# Sheet1.net
KiCad netlist of a schematic drawn in Altium Designer
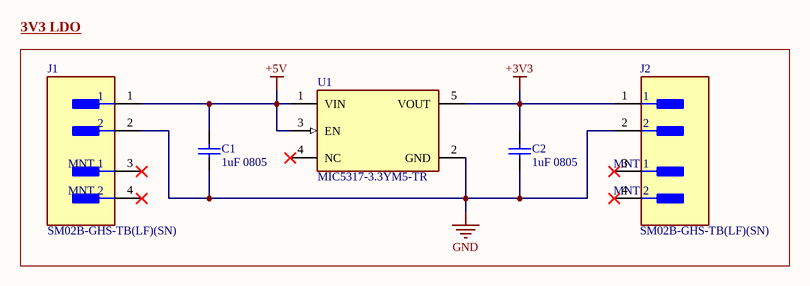
[diagram p0: Sheet1.SchDoc]

(export (version "E")
  (design (tool "Eeschema 10.0.6"))
  (components
    (comp (ref "C1")
      (value "1uF 0805")
      (footprint "CAPC2013X140X50NL20T25")
      (fields
        (field (name "PART NUMBER") "0805YD105MAT2A")
        (field (name "MANUFACTURER") "AVX Interconnect / Elco")
      )
      (libsource (lib "Altium Content Vault") (part "CAP"))
    )
    (comp (ref "C2")
      (value "1uF 0805")
      (footprint "CAPC2013X140X50NL20T25")
      (fields
        (field (name "PART NUMBER") "0805YD105MAT2A")
        (field (name "MANUFACTURER") "AVX Interconnect / Elco")
      )
      (libsource (lib "Altium Content Vault") (part "CAP"))
    )
    (comp (ref "J1")
      (value "SM02B-GHS-TB(LF)(SN)")
      (footprint "FP-SM02B-GHS-TB_LF_SN-MFG")
      (description "CONN HEADER SMD R/A 2POS 1.25MM")
      (libsource (lib "") (part "56ec3178a87b3978bdc1b3682cd516a_1"))
    )
    (comp (ref "J2")
      (value "SM02B-GHS-TB(LF)(SN)")
      (footprint "FP-SM02B-GHS-TB_LF_SN-MFG")
      (description "CONN HEADER SMD R/A 2POS 1.25MM")
      (libsource (lib "Altium Content Vault") (part "56ec3178a87b3978bdc1b3682cd516a"))
    )
    (comp (ref "U1")
      (value "MIC5317-3.3YM5-TR")
      (footprint "FP-SOT23-5LD-PL-1-MFG")
      (description "IC REG LINEAR 3.3V 150MA SOT23-5")
      (libsource (lib "Altium Content Vault") (part "0a093dae7315cdc977fd108dde87457"))
    )
  )
  (nets
    (net (code "1") (name "+3V3") (class "Default")
      (node (ref "C2") (pin "2") (pinfunction "2_2") (pintype "passive"))
      (node (ref "J2") (pin "1") (pinfunction "1_1") (pintype "passive"))
      (node (ref "U1") (pin "5") (pinfunction "VOUT_5") (pintype "power_in"))
    )
    (net (code "2") (name "+5V") (class "Default")
      (node (ref "C1") (pin "2") (pinfunction "2_2") (pintype "passive"))
      (node (ref "J1") (pin "1") (pinfunction "1_1") (pintype "passive"))
      (node (ref "U1") (pin "1") (pinfunction "VIN_1") (pintype "power_in"))
      (node (ref "U1") (pin "3") (pinfunction "EN_3") (pintype "input"))
    )
    (net (code "3") (name "GND") (class "Default")
      (node (ref "C1") (pin "1") (pinfunction "1_1") (pintype "passive"))
      (node (ref "C2") (pin "1") (pinfunction "1_1") (pintype "passive"))
      (node (ref "J1") (pin "2") (pinfunction "2_2") (pintype "passive"))
      (node (ref "J2") (pin "2") (pinfunction "2_2") (pintype "passive"))
      (node (ref "U1") (pin "2") (pinfunction "GND_2") (pintype "power_in"))
    )
    (net (code "4") (name "unconnected-(J1-MNT_1-Pad3)") (class "Default")
      (node (ref "J1") (pin "3") (pinfunction "MNT_1_3") (pintype "passive+no_connect"))
    )
    (net (code "5") (name "unconnected-(J1-MNT_2-Pad4)") (class "Default")
      (node (ref "J1") (pin "4") (pinfunction "MNT_2_4") (pintype "passive+no_connect"))
    )
    (net (code "6") (name "unconnected-(J2-MNT_1-Pad3)") (class "Default")
      (node (ref "J2") (pin "3") (pinfunction "MNT_1_3") (pintype "passive+no_connect"))
    )
    (net (code "7") (name "unconnected-(J2-MNT_2-Pad4)") (class "Default")
      (node (ref "J2") (pin "4") (pinfunction "MNT_2_4") (pintype "passive+no_connect"))
    )
    (net (code "8") (name "unconnected-(U1-NC-Pad4)") (class "Default")
      (node (ref "U1") (pin "4") (pinfunction "NC_4") (pintype "passive+no_connect"))
    )
  )
)
